# ps2.net
KiCad netlist of a schematic drawn in EAGLE
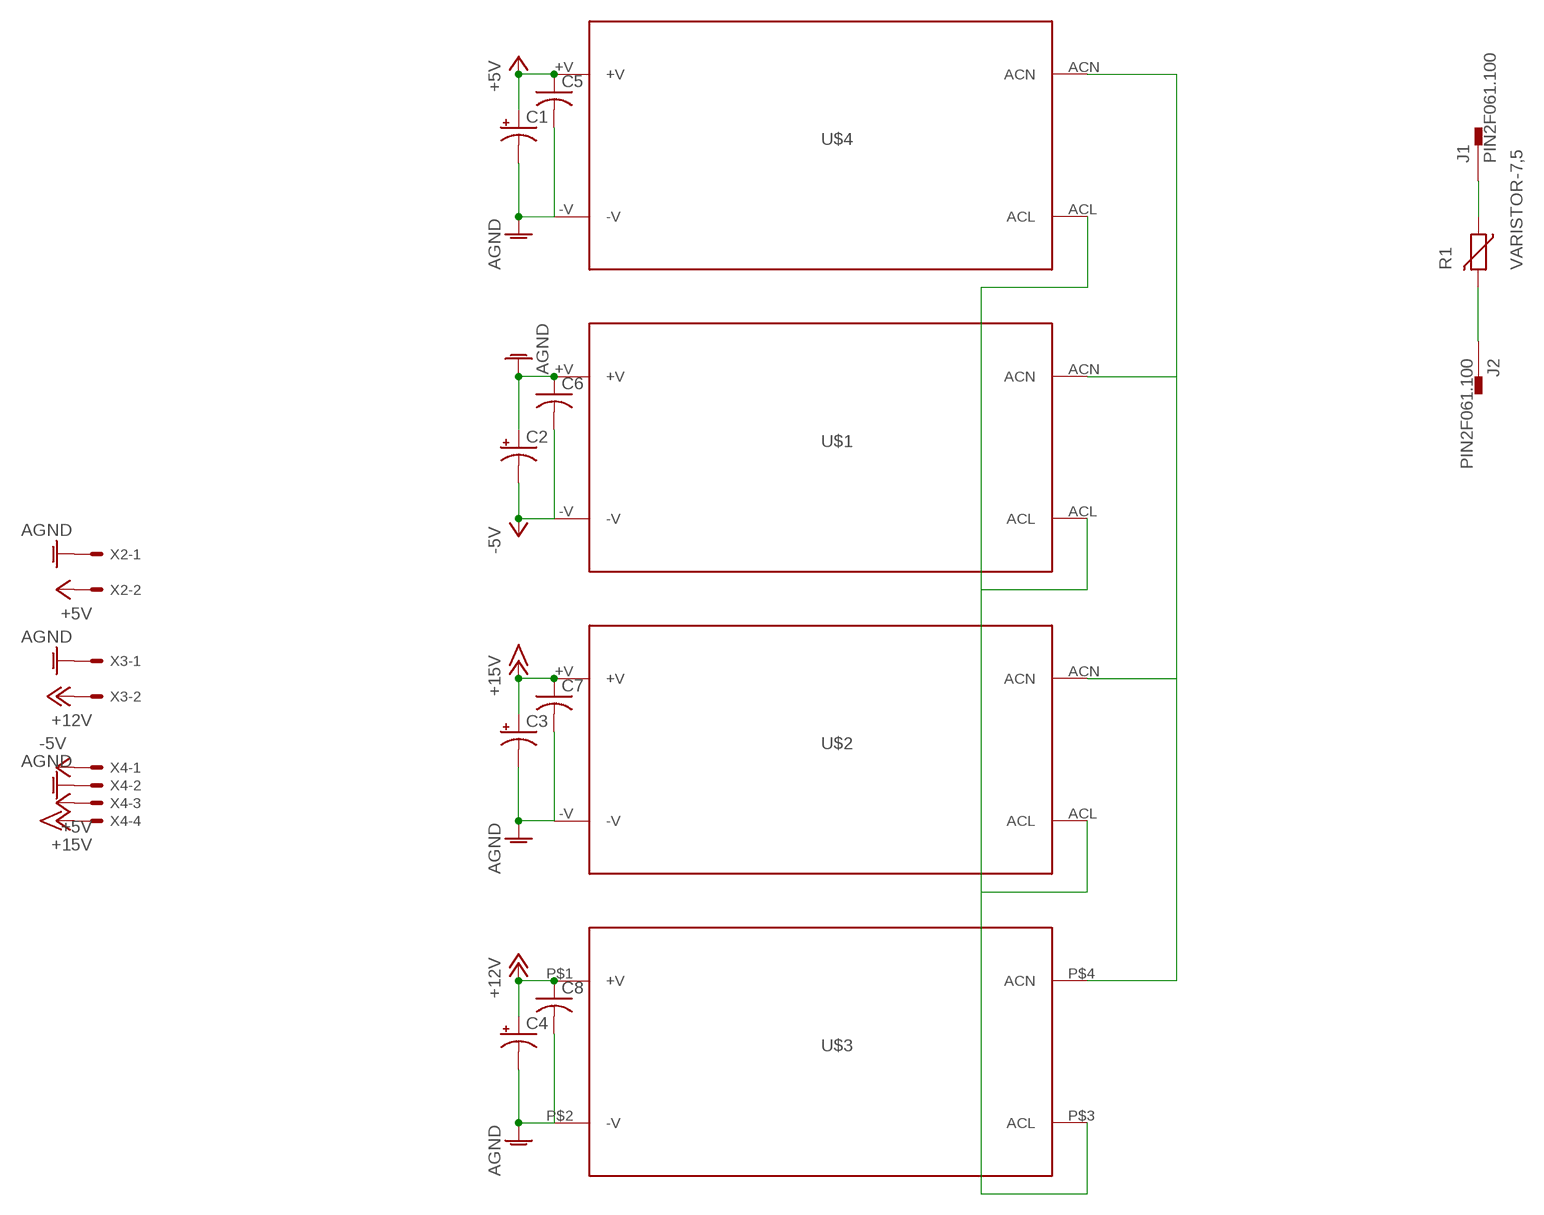
[diagram p0: schematic, sheet 1]

(export (version "E")
  (design (tool "Eeschema 10.0.6"))
  (components
    (comp (ref "C1")
      (value "CPOL-USE10-22.5")
      (footprint "eagle-import:EB22,5D")
      (libsource (lib "eagle-import") (part "CPOL-USE10-22.5"))
    )
    (comp (ref "C2")
      (value "CPOL-USE10-22.5")
      (footprint "eagle-import:EB22,5D")
      (libsource (lib "eagle-import") (part "CPOL-USE10-22.5"))
    )
    (comp (ref "C3")
      (value "CPOL-USE10-22.5")
      (footprint "eagle-import:EB22,5D")
      (libsource (lib "eagle-import") (part "CPOL-USE10-22.5"))
    )
    (comp (ref "C4")
      (value "CPOL-USE10-22.5")
      (footprint "eagle-import:EB22,5D")
      (libsource (lib "eagle-import") (part "CPOL-USE10-22.5"))
    )
    (comp (ref "C5")
      (value "C-US075-052X106")
      (footprint "eagle-import:C075-052X106")
      (libsource (lib "eagle-import") (part "C-US075-052X106"))
    )
    (comp (ref "C6")
      (value "C-US075-052X106")
      (footprint "eagle-import:C075-052X106")
      (libsource (lib "eagle-import") (part "C-US075-052X106"))
    )
    (comp (ref "C7")
      (value "C-US075-052X106")
      (footprint "eagle-import:C075-052X106")
      (libsource (lib "eagle-import") (part "C-US075-052X106"))
    )
    (comp (ref "C8")
      (value "C-US075-052X106")
      (footprint "eagle-import:C075-052X106")
      (libsource (lib "eagle-import") (part "C-US075-052X106"))
    )
    (comp (ref "J1")
      (value "PIN2F061.100")
      (footprint "eagle-import:F061.100")
      (libsource (lib "eagle-import") (part "PIN2F061.100"))
    )
    (comp (ref "J2")
      (value "PIN2F061.100")
      (footprint "eagle-import:F061.100")
      (libsource (lib "eagle-import") (part "PIN2F061.100"))
    )
    (comp (ref "R1")
      (value "VARISTOR-7,5")
      (footprint "eagle-import:R-7,5")
      (libsource (lib "eagle-import") (part "VARISTOR-7,5"))
    )
    (comp (ref "U$1")
      (value "IRM-30-5")
      (footprint "eagle-import:IRM-30-15")
      (libsource (lib "eagle-import") (part "IRM-30-5"))
    )
    (comp (ref "U$2")
      (value "IRM-30-15")
      (footprint "eagle-import:IRM-30-15")
      (libsource (lib "eagle-import") (part "IRM-30-15"))
    )
    (comp (ref "U$3")
      (value "IRM-60-12")
      (footprint "eagle-import:IRM-60-12")
      (libsource (lib "eagle-import") (part "IRM-60-12"))
    )
    (comp (ref "U$4")
      (value "IRM-30-5")
      (footprint "eagle-import:IRM-30-15")
      (libsource (lib "eagle-import") (part "IRM-30-5"))
    )
    (comp (ref "X2")
      (value "KK-156-2")
      (footprint "eagle-import:KK-156-2")
      (libsource (lib "eagle-import") (part "KK-156-2"))
    )
    (comp (ref "X3")
      (value "KK-156-2")
      (footprint "eagle-import:KK-156-2")
      (libsource (lib "eagle-import") (part "KK-156-2"))
    )
    (comp (ref "X4")
      (value "KK-156-4")
      (footprint "eagle-import:KK-156-4")
      (libsource (lib "eagle-import") (part "KK-156-4"))
    )
  )
  (nets
    (net (code "1") (name "+5V") (class "Default")
      (node (ref "C1") (pin "+") (pinfunction "+_+") (pintype "passive"))
      (node (ref "C5") (pin "1") (pinfunction "1_1") (pintype "passive"))
      (node (ref "U$4") (pin "+V") (pinfunction "+V_+V") (pintype "bidirectional"))
      (node (ref "X2") (pin "2") (pinfunction "S_2") (pintype "passive"))
      (node (ref "X4") (pin "3") (pinfunction "S_3") (pintype "passive"))
    )
    (net (code "2") (name "+12V") (class "Default")
      (node (ref "C4") (pin "+") (pinfunction "+_+") (pintype "passive"))
      (node (ref "C8") (pin "1") (pinfunction "1_1") (pintype "passive"))
      (node (ref "U$3") (pin "P$1") (pinfunction "+V_P$1") (pintype "bidirectional"))
      (node (ref "X3") (pin "2") (pinfunction "S_2") (pintype "passive"))
    )
    (net (code "3") (name "+15V") (class "Default")
      (node (ref "C3") (pin "+") (pinfunction "+_+") (pintype "passive"))
      (node (ref "C7") (pin "1") (pinfunction "1_1") (pintype "passive"))
      (node (ref "U$2") (pin "+V") (pinfunction "+V_+V") (pintype "bidirectional"))
      (node (ref "X4") (pin "4") (pinfunction "S_4") (pintype "passive"))
    )
    (net (code "4") (name "-5V") (class "Default")
      (node (ref "C2") (pin "-") (pinfunction "-_-") (pintype "passive"))
      (node (ref "C6") (pin "2") (pinfunction "2_2") (pintype "passive"))
      (node (ref "U$1") (pin "-V") (pinfunction "-V_-V") (pintype "bidirectional"))
      (node (ref "X4") (pin "1") (pinfunction "S_1") (pintype "passive"))
    )
    (net (code "5") (name "/ACL") (class "Default")
      (node (ref "J1") (pin "A1") (pinfunction "1_A1") (pintype "passive"))
      (node (ref "J1") (pin "A2") (pinfunction "1_A2") (pintype "passive"))
      (node (ref "R1") (pin "1") (pinfunction "1_1") (pintype "passive"))
      (node (ref "U$1") (pin "ACL") (pinfunction "ACL_ACL") (pintype "bidirectional"))
      (node (ref "U$2") (pin "ACL") (pinfunction "ACL_ACL") (pintype "bidirectional"))
      (node (ref "U$3") (pin "P$3") (pinfunction "ACL_P$3") (pintype "bidirectional"))
      (node (ref "U$4") (pin "ACL") (pinfunction "ACL_ACL") (pintype "bidirectional"))
    )
    (net (code "6") (name "/ACN") (class "Default")
      (node (ref "J2") (pin "A1") (pinfunction "1_A1") (pintype "passive"))
      (node (ref "J2") (pin "A2") (pinfunction "1_A2") (pintype "passive"))
      (node (ref "R1") (pin "2") (pinfunction "2_2") (pintype "passive"))
      (node (ref "U$1") (pin "ACN") (pinfunction "ACN_ACN") (pintype "bidirectional"))
      (node (ref "U$2") (pin "ACN") (pinfunction "ACN_ACN") (pintype "bidirectional"))
      (node (ref "U$3") (pin "P$4") (pinfunction "ACN_P$4") (pintype "bidirectional"))
      (node (ref "U$4") (pin "ACN") (pinfunction "ACN_ACN") (pintype "bidirectional"))
    )
    (net (code "7") (name "AGND") (class "Default")
      (node (ref "C1") (pin "-") (pinfunction "-_-") (pintype "passive"))
      (node (ref "C2") (pin "+") (pinfunction "+_+") (pintype "passive"))
      (node (ref "C3") (pin "-") (pinfunction "-_-") (pintype "passive"))
      (node (ref "C4") (pin "-") (pinfunction "-_-") (pintype "passive"))
      (node (ref "C5") (pin "2") (pinfunction "2_2") (pintype "passive"))
      (node (ref "C6") (pin "1") (pinfunction "1_1") (pintype "passive"))
      (node (ref "C7") (pin "2") (pinfunction "2_2") (pintype "passive"))
      (node (ref "C8") (pin "2") (pinfunction "2_2") (pintype "passive"))
      (node (ref "U$1") (pin "+V") (pinfunction "+V_+V") (pintype "bidirectional"))
      (node (ref "U$2") (pin "-V") (pinfunction "-V_-V") (pintype "bidirectional"))
      (node (ref "U$3") (pin "P$2") (pinfunction "-V_P$2") (pintype "bidirectional"))
      (node (ref "U$4") (pin "-V") (pinfunction "-V_-V") (pintype "bidirectional"))
      (node (ref "X2") (pin "1") (pinfunction "S_1") (pintype "passive"))
      (node (ref "X3") (pin "1") (pinfunction "S_1") (pintype "passive"))
      (node (ref "X4") (pin "2") (pinfunction "S_2") (pintype "passive"))
    )
  )
)
